# 6coils-transistor.net
KiCad netlist of a schematic drawn in EasyEDA
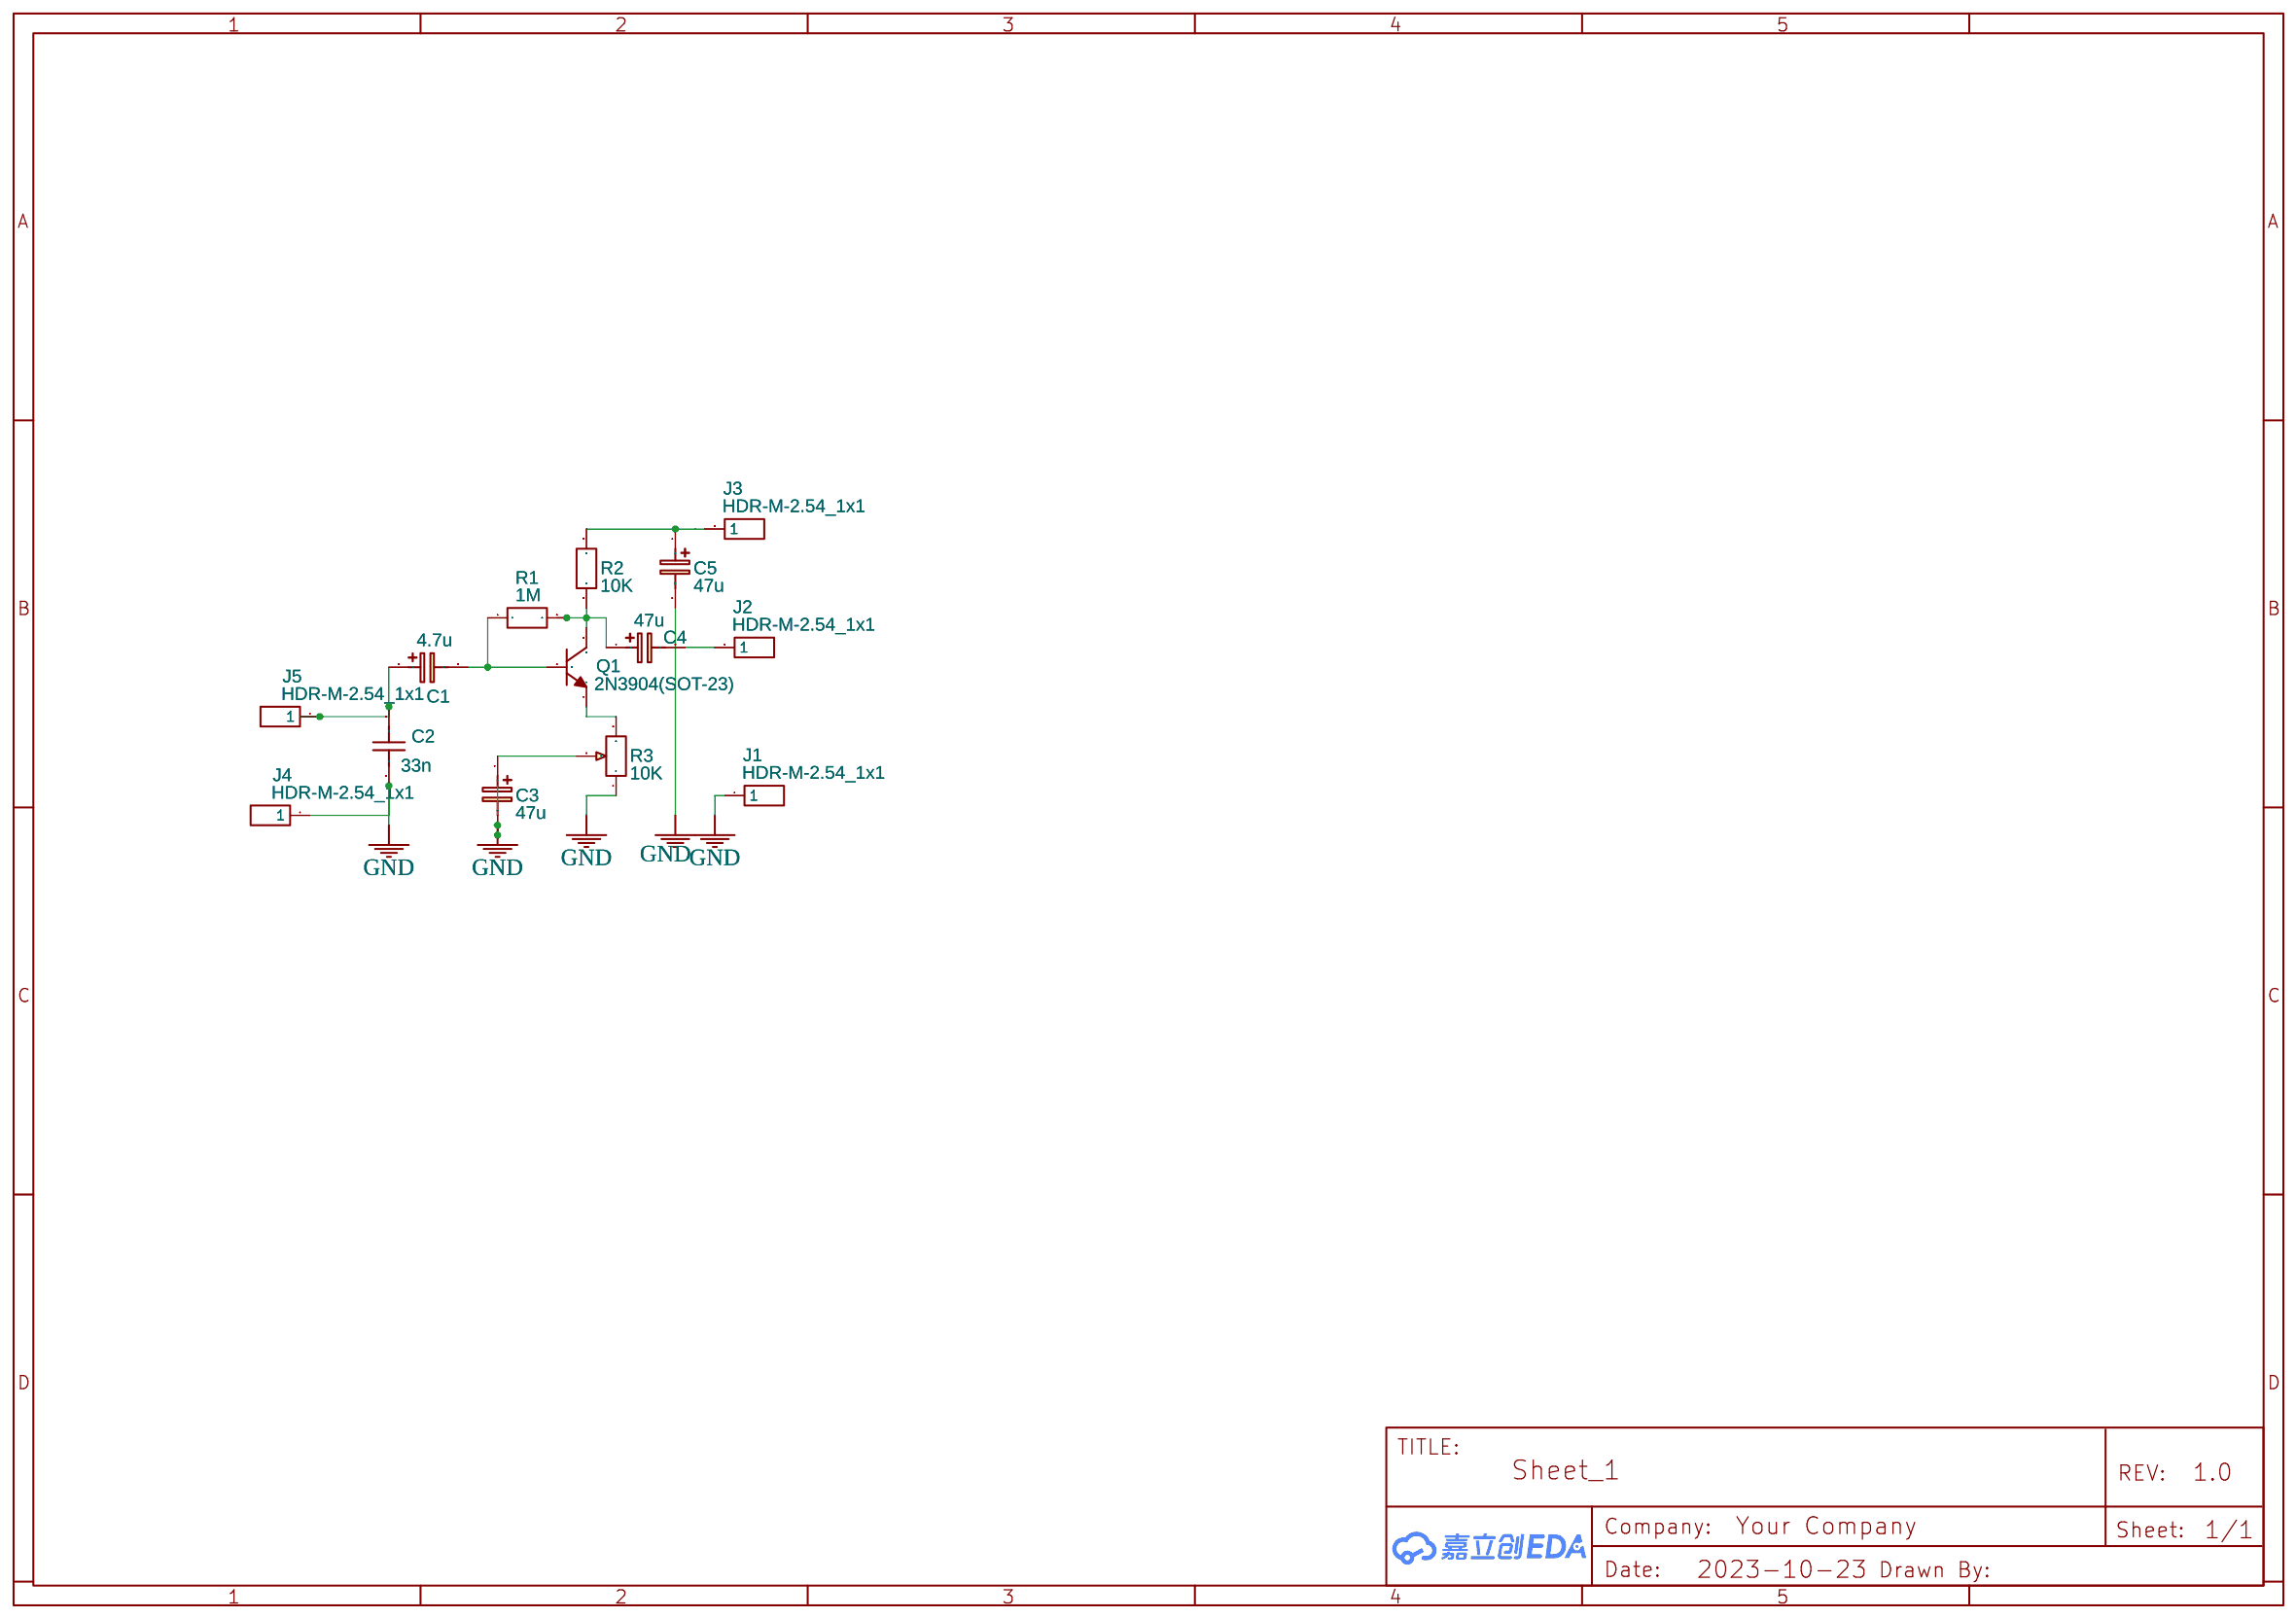
[diagram p0: schematic sheet]

(export (version "E")
  (design (tool "Eeschema 10.0.6"))
  (components
    (comp (ref "C1") (value "4.7u") (libsource (lib "") (part "C_Tan_SMD_A_EU")))
    (comp (ref "C2") (value "33n") (libsource (lib "") (part "C_0603_US")))
    (comp (ref "C3") (value "47u") (libsource (lib "") (part "C_Tan_SMD_A_EU_2")))
    (comp (ref "C4") (value "47u") (libsource (lib "") (part "C_Tan_SMD_A_EU_3")))
    (comp (ref "C5") (value "47u") (libsource (lib "") (part "C_Tan_SMD_A_EU_1")))
    (comp (ref "J1")
      (value "HDR-M-2.54_1x1")
      (fields (field (name "BOM_Supplier Part") "C81276"))
      (libsource (lib "") (part "HDR-M-2.54_1x1_1"))
    )
    (comp (ref "J2")
      (value "HDR-M-2.54_1x1")
      (fields (field (name "BOM_Supplier Part") "C81276"))
      (libsource (lib "") (part "HDR-M-2.54_1x1_1"))
    )
    (comp (ref "J3")
      (value "HDR-M-2.54_1x1")
      (fields (field (name "BOM_Supplier Part") "C81276"))
      (libsource (lib "") (part "HDR-M-2.54_1x1_1"))
    )
    (comp (ref "J4")
      (value "HDR-M-2.54_1x1")
      (fields (field (name "BOM_Supplier Part") "C81276"))
      (libsource (lib "") (part "HDR-M-2.54_1x1"))
    )
    (comp (ref "J5")
      (value "HDR-M-2.54_1x1")
      (fields (field (name "BOM_Supplier Part") "C81276"))
      (libsource (lib "") (part "HDR-M-2.54_1x1"))
    )
    (comp (ref "Q1")
      (value "2N3904(SOT-23)")
      (fields
        (field (name "BOM_Manufacturer Part") "2n3904S-RTK/PS")
        (field (name "BOM_Supplier Part") "C18536")
      )
      (libsource (lib "") (part "2N3904(SOT-23)"))
    )
    (comp (ref "R1") (value "1M") (libsource (lib "") (part "R_0603_EU")))
    (comp (ref "R2") (value "10K") (libsource (lib "") (part "R_0603_EU_1")))
    (comp (ref "R3")
      (value "10K")
      (fields (field (name "Manufacturer Part") "RM063-103 10K") (field (name "Manufacturer") "JML"))
      (libsource (lib "") (part "RM063-103 10K"))
    )
  )
  (nets
    (net (code "1") (name "GND") (class "Default")
      (node (ref "C2") (pin "1") (pinfunction "1_1") (pintype "unspecified"))
      (node (ref "C3") (pin "2") (pinfunction "2_2") (pintype "unspecified"))
      (node (ref "C5") (pin "2") (pinfunction "2_2") (pintype "unspecified"))
      (node (ref "J1") (pin "1") (pinfunction "1_1") (pintype "input"))
      (node (ref "J4") (pin "1") (pinfunction "1_1") (pintype "input"))
      (node (ref "R3") (pin "1") (pinfunction "1_1") (pintype "input"))
    )
    (net (code "2") (name "Net-(C1-Pad1)") (class "Default")
      (node (ref "C1") (pin "1") (pinfunction "1_1") (pintype "unspecified"))
      (node (ref "C2") (pin "2") (pinfunction "2_2") (pintype "unspecified"))
      (node (ref "J5") (pin "1") (pinfunction "1_1") (pintype "input"))
    )
    (net (code "3") (name "Net-(C3-Pad1)") (class "Default")
      (node (ref "C3") (pin "1") (pinfunction "1_1") (pintype "unspecified"))
      (node (ref "R3") (pin "2") (pinfunction "2_2") (pintype "input"))
    )
    (net (code "4") (name "Net-(C4-Pad2)") (class "Default")
      (node (ref "C4") (pin "2") (pinfunction "2_2") (pintype "unspecified"))
      (node (ref "J2") (pin "1") (pinfunction "1_1") (pintype "input"))
    )
    (net (code "5") (name "Net-(C5-Pad1)") (class "Default")
      (node (ref "C5") (pin "1") (pinfunction "1_1") (pintype "unspecified"))
      (node (ref "J3") (pin "1") (pinfunction "1_1") (pintype "input"))
      (node (ref "R2") (pin "2") (pinfunction "2_2") (pintype "unspecified"))
    )
    (net (code "6") (name "Net-(Q1-B)") (class "Default")
      (node (ref "C1") (pin "2") (pinfunction "2_2") (pintype "unspecified"))
      (node (ref "Q1") (pin "2") (pinfunction "B_2") (pintype "input"))
      (node (ref "R1") (pin "1") (pinfunction "1_1") (pintype "unspecified"))
    )
    (net (code "7") (name "Net-(Q1-C)") (class "Default")
      (node (ref "C4") (pin "1") (pinfunction "1_1") (pintype "unspecified"))
      (node (ref "Q1") (pin "3") (pinfunction "C_3") (pintype "input"))
      (node (ref "R1") (pin "2") (pinfunction "2_2") (pintype "unspecified"))
      (node (ref "R2") (pin "1") (pinfunction "1_1") (pintype "unspecified"))
    )
    (net (code "8") (name "Net-(Q1-E)") (class "Default")
      (node (ref "Q1") (pin "1") (pinfunction "E_1") (pintype "input"))
      (node (ref "R3") (pin "3") (pinfunction "3_3") (pintype "input"))
    )
  )
)
